# fuzz.net
KiCad netlist of a schematic drawn in EAGLE
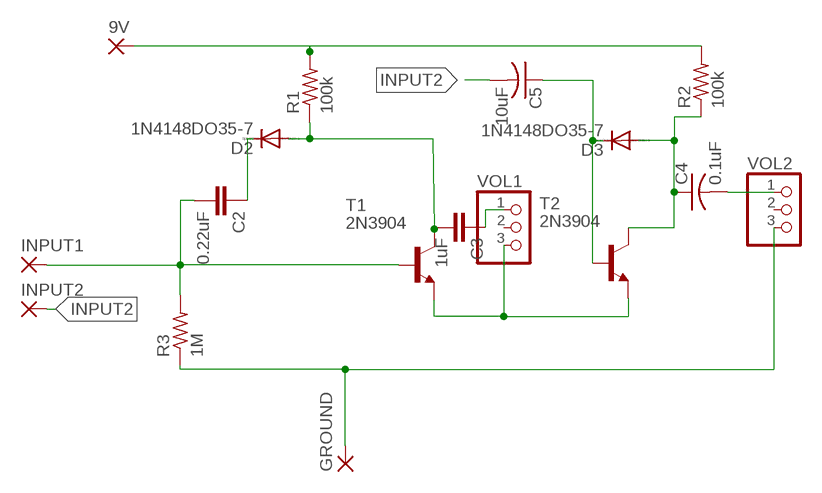
[diagram p0: schematic, sheet 1]

(export (version "E")
  (design (tool "Eeschema 10.0.6"))
  (components
    (comp (ref "9V")
      (value "2,15/1,0")
      (footprint "eagle-import:2,15_1,0")
      (libsource (lib "eagle-import") (part "2,15/1,0"))
    )
    (comp (ref "C2")
      (value "0.22uF")
      (footprint "eagle-import:C025-025X050")
      (libsource (lib "eagle-import") (part "C-EU025-025X050"))
    )
    (comp (ref "C3")
      (value "1uF")
      (footprint "eagle-import:C025-025X050")
      (libsource (lib "eagle-import") (part "C-EU025-025X050"))
    )
    (comp (ref "C4")
      (value "0.1uF")
      (footprint "eagle-import:C025-025X050")
      (libsource (lib "eagle-import") (part "C-US025-025X050"))
    )
    (comp (ref "C5")
      (value "10uF")
      (footprint "eagle-import:C025-025X050")
      (libsource (lib "eagle-import") (part "C-US025-025X050"))
    )
    (comp (ref "D2")
      (value "1N4148DO35-7")
      (footprint "eagle-import:DO35-7")
      (libsource (lib "eagle-import") (part "1N4148DO35-7"))
    )
    (comp (ref "D3")
      (value "1N4148DO35-7")
      (footprint "eagle-import:DO35-7")
      (libsource (lib "eagle-import") (part "1N4148DO35-7"))
    )
    (comp (ref "GROUND")
      (value "2,15/1,0")
      (footprint "eagle-import:2,15_1,0")
      (libsource (lib "eagle-import") (part "2,15/1,0"))
    )
    (comp (ref "INPUT1")
      (value "2,15/1,0")
      (footprint "eagle-import:2,15_1,0")
      (libsource (lib "eagle-import") (part "2,15/1,0"))
    )
    (comp (ref "INPUT2")
      (value "2,15/1,0")
      (footprint "eagle-import:2,15_1,0")
      (libsource (lib "eagle-import") (part "2,15/1,0"))
    )
    (comp (ref "R1")
      (value "100k")
      (footprint "eagle-import:0207_10")
      (libsource (lib "eagle-import") (part "R-US_0207/10"))
    )
    (comp (ref "R2")
      (value "100k")
      (footprint "eagle-import:0207_10")
      (libsource (lib "eagle-import") (part "R-US_0207/10"))
    )
    (comp (ref "R3")
      (value "1M")
      (footprint "eagle-import:0207_10")
      (libsource (lib "eagle-import") (part "R-US_0207/10"))
    )
    (comp (ref "T1")
      (value "2N3904")
      (footprint "eagle-import:TO92")
      (libsource (lib "eagle-import") (part "2N3904"))
    )
    (comp (ref "T2")
      (value "2N3904")
      (footprint "eagle-import:TO92")
      (libsource (lib "eagle-import") (part "2N3904"))
    )
    (comp (ref "VOL1")
      (value "PINHD-1X3")
      (footprint "eagle-import:1X03")
      (libsource (lib "eagle-import") (part "PINHD-1X3"))
    )
    (comp (ref "VOL2")
      (value "PINHD-1X3")
      (footprint "eagle-import:1X03")
      (libsource (lib "eagle-import") (part "PINHD-1X3"))
    )
  )
  (nets
    (net (code "1") (name "INPUT2") (class "Default")
      (node (ref "C5") (pin "2") (pinfunction "2_2") (pintype "passive"))
      (node (ref "INPUT2") (pin "1") (pinfunction "P_1") (pintype "passive"))
    )
    (net (code "2") (name "Net-(9V-P)") (class "Default")
      (node (ref "9V") (pin "1") (pinfunction "P_1") (pintype "passive"))
      (node (ref "R1") (pin "2") (pinfunction "2_2") (pintype "passive"))
      (node (ref "R2") (pin "2") (pinfunction "2_2") (pintype "passive"))
    )
    (net (code "3") (name "Net-(C2-Pad1)") (class "Default")
      (node (ref "C2") (pin "1") (pinfunction "1_1") (pintype "passive"))
      (node (ref "D2") (pin "C") (pinfunction "C_C") (pintype "passive"))
    )
    (net (code "4") (name "Net-(C3-Pad1)") (class "Default")
      (node (ref "C3") (pin "1") (pinfunction "1_1") (pintype "passive"))
      (node (ref "VOL1") (pin "1") (pinfunction "1_1") (pintype "passive"))
    )
    (net (code "5") (name "Net-(C4-Pad2)") (class "Default")
      (node (ref "C4") (pin "2") (pinfunction "2_2") (pintype "passive"))
      (node (ref "VOL2") (pin "1") (pinfunction "1_1") (pintype "passive"))
    )
    (net (code "6") (name "Net-(GROUND-P)") (class "Default")
      (node (ref "GROUND") (pin "1") (pinfunction "P_1") (pintype "passive"))
      (node (ref "R3") (pin "1") (pinfunction "1_1") (pintype "passive"))
      (node (ref "VOL2") (pin "3") (pinfunction "3_3") (pintype "passive"))
    )
    (net (code "7") (name "Net-(INPUT1-P)") (class "Default")
      (node (ref "C2") (pin "2") (pinfunction "2_2") (pintype "passive"))
      (node (ref "INPUT1") (pin "1") (pinfunction "P_1") (pintype "passive"))
      (node (ref "R3") (pin "2") (pinfunction "2_2") (pintype "passive"))
      (node (ref "T1") (pin "2") (pinfunction "B_2") (pintype "passive"))
    )
    (net (code "8") (name "Net-(T1-C)") (class "Default")
      (node (ref "C3") (pin "2") (pinfunction "2_2") (pintype "passive"))
      (node (ref "D2") (pin "A") (pinfunction "A_A") (pintype "passive"))
      (node (ref "R1") (pin "1") (pinfunction "1_1") (pintype "passive"))
      (node (ref "T1") (pin "1") (pinfunction "C_1") (pintype "passive"))
    )
    (net (code "9") (name "Net-(T1-E)") (class "Default")
      (node (ref "T1") (pin "3") (pinfunction "E_3") (pintype "passive"))
      (node (ref "T2") (pin "3") (pinfunction "E_3") (pintype "passive"))
      (node (ref "VOL1") (pin "3") (pinfunction "3_3") (pintype "passive"))
    )
    (net (code "10") (name "Net-(T2-B)") (class "Default")
      (node (ref "C5") (pin "1") (pinfunction "1_1") (pintype "passive"))
      (node (ref "D3") (pin "C") (pinfunction "C_C") (pintype "passive"))
      (node (ref "T2") (pin "2") (pinfunction "B_2") (pintype "passive"))
    )
    (net (code "11") (name "Net-(T2-C)") (class "Default")
      (node (ref "C4") (pin "1") (pinfunction "1_1") (pintype "passive"))
      (node (ref "D3") (pin "A") (pinfunction "A_A") (pintype "passive"))
      (node (ref "R2") (pin "1") (pinfunction "1_1") (pintype "passive"))
      (node (ref "T2") (pin "1") (pinfunction "C_1") (pintype "passive"))
    )
    (net (code "12") (name "unconnected-(VOL1-Pad2)") (class "Default")
      (node (ref "VOL1") (pin "2") (pinfunction "2_2") (pintype "passive"))
    )
    (net (code "13") (name "unconnected-(VOL2-Pad2)") (class "Default")
      (node (ref "VOL2") (pin "2") (pinfunction "2_2") (pintype "passive"))
    )
  )
)
